# NG2092_RIGHT_OV9282.net
KiCad netlist of a schematic drawn in Altium Designer
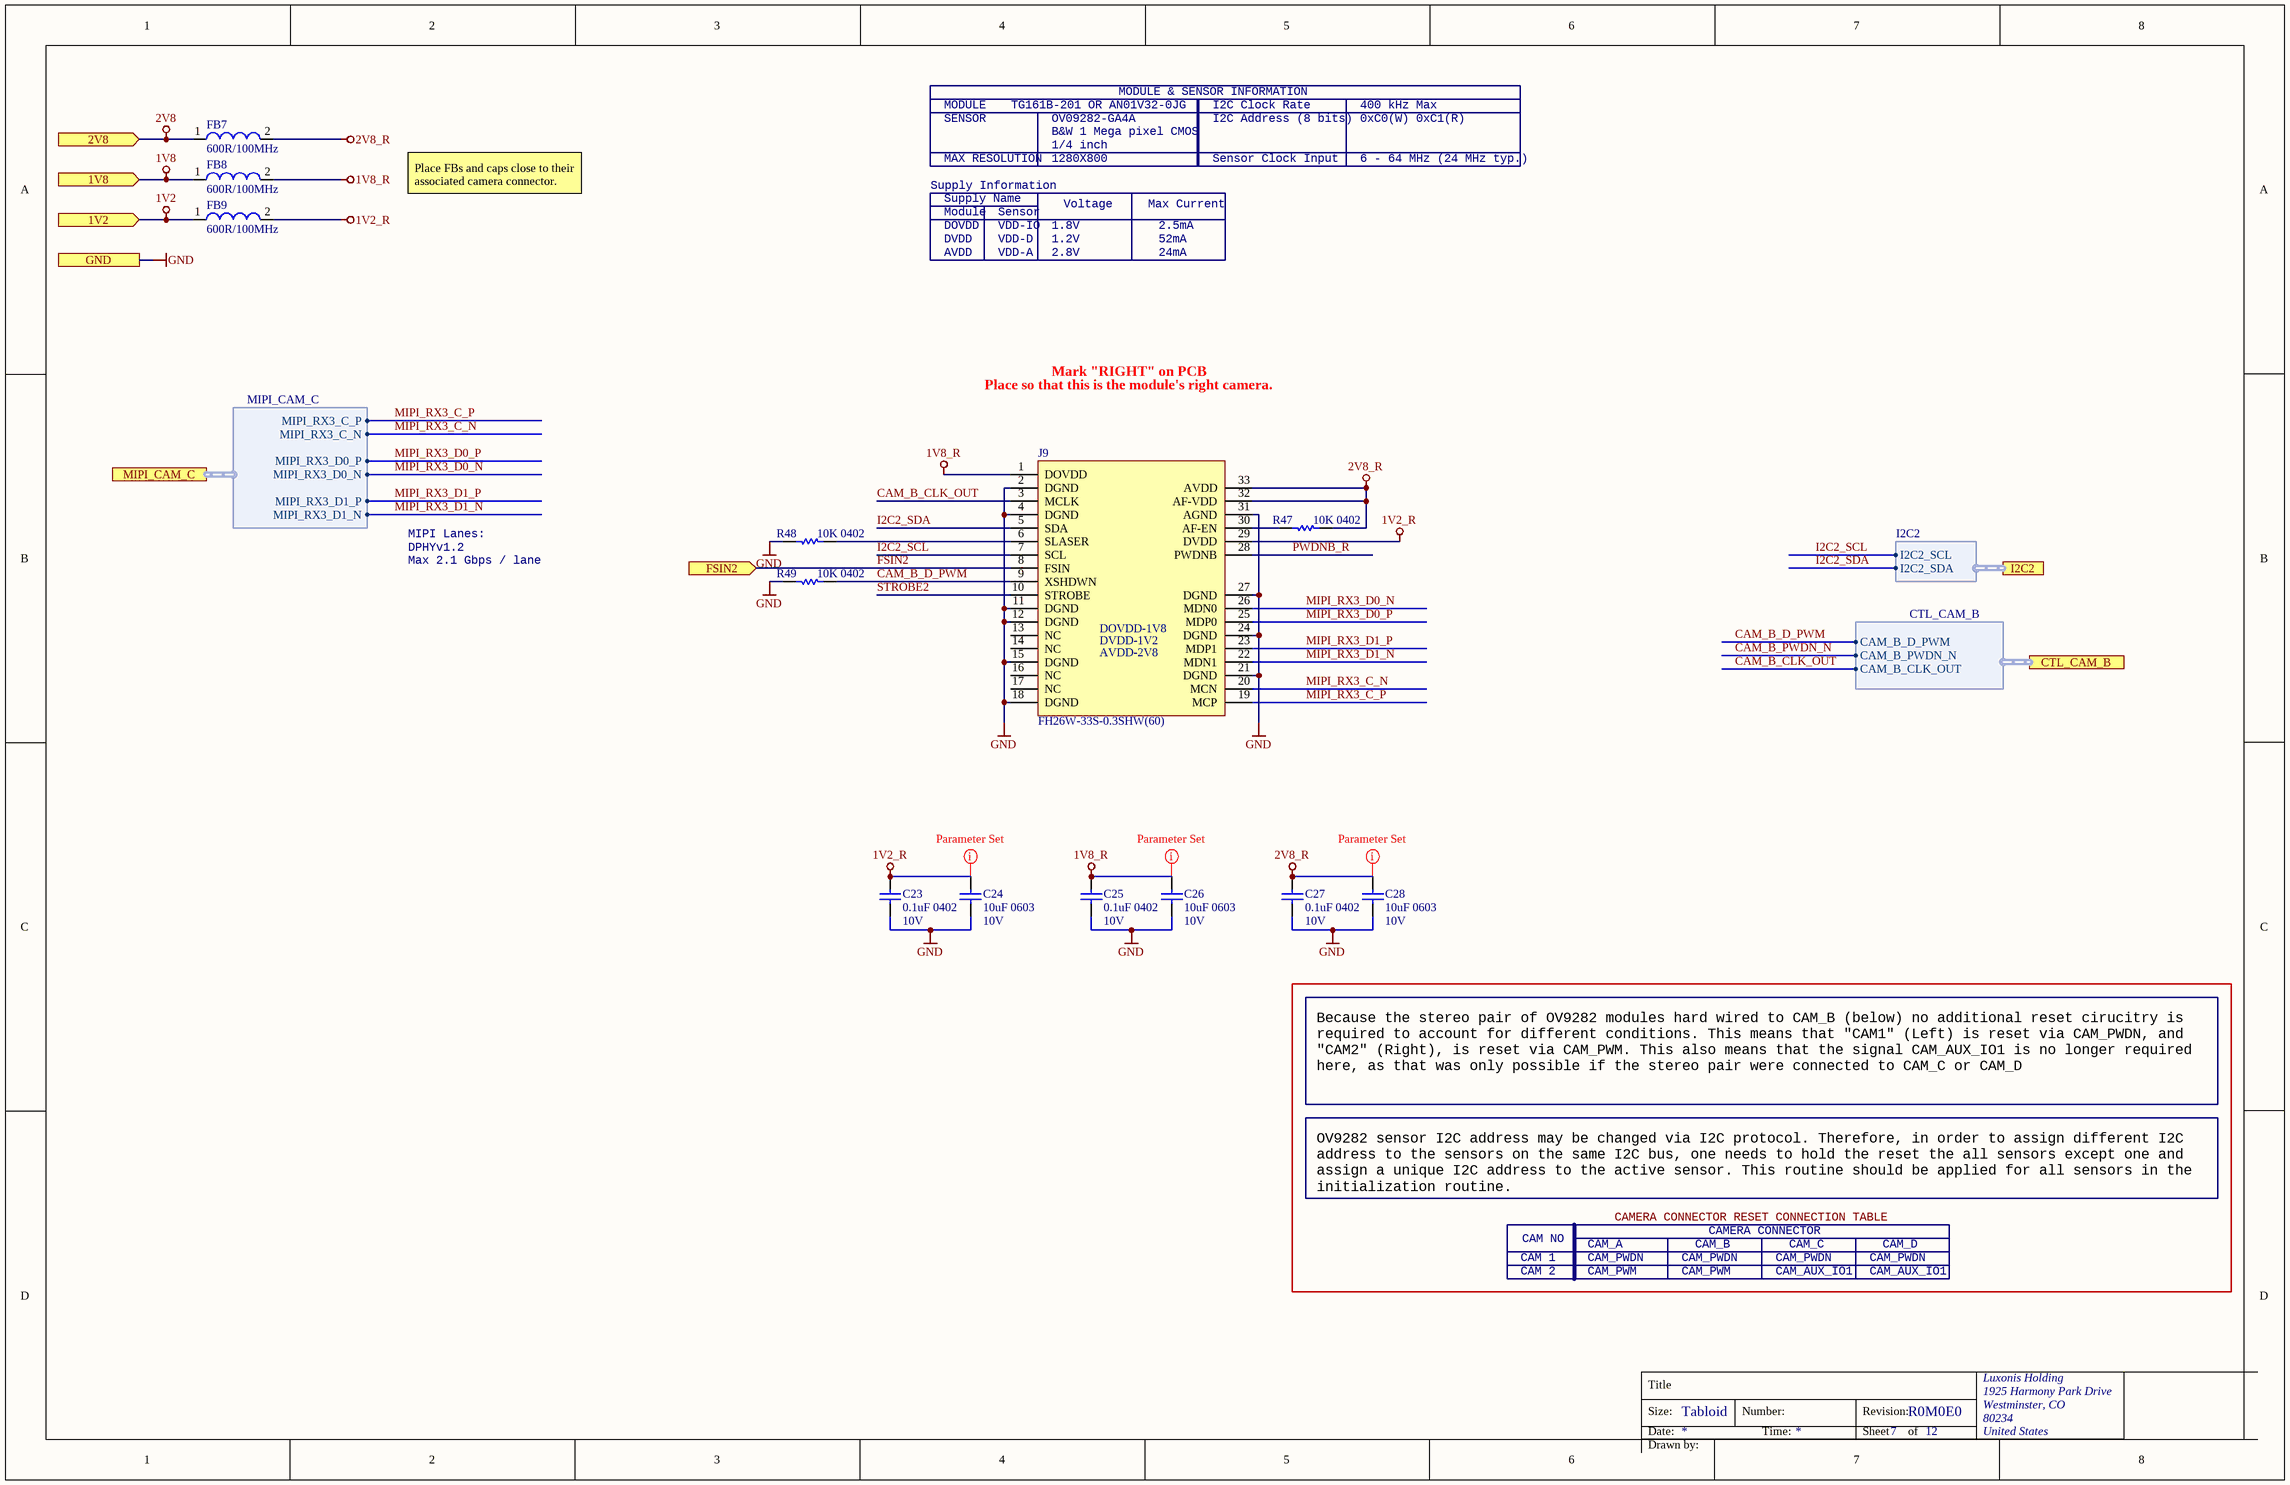
[diagram p0: NG2092_RIGHT_OV9282.SchDoc]

(export (version "E")
  (design (tool "Eeschema 10.0.6"))
  (components
    (comp (ref "C23")
      (value "0.1uF 0402")
      (footprint "CAP_Altium_Vault_Generic:CAPC0402(1005)70_L")
      (description "CAP CER 0.1UF 10V X7R 0402 5%")
      (fields (field (name "TOLERANCE") "5%") (field (name "VOLTAGE RATING") "10V"))
      (libsource (lib "LuxonisMaster") (part "GRM155R71A104JA01D"))
    )
    (comp (ref "C24")
      (value "10uF 0603")
      (footprint "CAP_Altium_Vault_Generic:CAPC0603(1608)100_L")
      (description "CAP CER 10UF 10V X5R 0603 20%")
      (fields (field (name "TOLERANCE") "20%") (field (name "VOLTAGE RATING") "10V"))
      (libsource (lib "LuxonisMaster") (part "GRM188R61A106ME69D"))
    )
    (comp (ref "C25")
      (value "0.1uF 0402")
      (footprint "CAP_Altium_Vault_Generic:CAPC0402(1005)70_L")
      (description "CAP CER 0.1UF 10V X7R 0402 5%")
      (fields (field (name "TOLERANCE") "5%") (field (name "VOLTAGE RATING") "10V"))
      (libsource (lib "LuxonisMaster") (part "GRM155R71A104JA01D"))
    )
    (comp (ref "C26")
      (value "10uF 0603")
      (footprint "CAP_Altium_Vault_Generic:CAPC0603(1608)100_L")
      (description "CAP CER 10UF 10V X5R 0603 20%")
      (fields (field (name "TOLERANCE") "20%") (field (name "VOLTAGE RATING") "10V"))
      (libsource (lib "LuxonisMaster") (part "GRM188R61A106ME69D"))
    )
    (comp (ref "C27")
      (value "0.1uF 0402")
      (footprint "CAP_Altium_Vault_Generic:CAPC0402(1005)70_L")
      (description "CAP CER 0.1UF 10V X7R 0402 5%")
      (fields (field (name "TOLERANCE") "5%") (field (name "VOLTAGE RATING") "10V"))
      (libsource (lib "LuxonisMaster") (part "GRM155R71A104JA01D"))
    )
    (comp (ref "C28")
      (value "10uF 0603")
      (footprint "CAP_Altium_Vault_Generic:CAPC0603(1608)100_L")
      (description "CAP CER 10UF 10V X5R 0603 20%")
      (fields (field (name "TOLERANCE") "20%") (field (name "VOLTAGE RATING") "10V"))
      (libsource (lib "LuxonisMaster") (part "GRM188R61A106ME69D"))
    )
    (comp (ref "FB7")
      (value "600R/100MHz")
      (footprint "LuxonisMaster:2508056017Y2")
      (description "FERRITE BEAD, 0.1OHM, 2A, 0805, 600R/100MHz")
      (fields (field (name "TOLERANCE") "25%"))
      (libsource (lib "LuxonisMaster") (part "2508056017Y2"))
    )
    (comp (ref "FB8")
      (value "600R/100MHz")
      (footprint "LuxonisMaster:2508056017Y2")
      (description "FERRITE BEAD, 0.1OHM, 2A, 0805, 600R/100MHz")
      (fields (field (name "TOLERANCE") "25%"))
      (libsource (lib "LuxonisMaster") (part "2508056017Y2"))
    )
    (comp (ref "FB9")
      (value "600R/100MHz")
      (footprint "LuxonisMaster:2508056017Y2")
      (description "FERRITE BEAD, 0.1OHM, 2A, 0805, 600R/100MHz")
      (fields (field (name "TOLERANCE") "25%"))
      (libsource (lib "LuxonisMaster") (part "2508056017Y2"))
    )
    (comp (ref "J9")
      (value "FH26W-33S-0.3SHW(60)")
      (footprint "AC-PY003-OV9282")
      (description "FFC/FPC Connector, 33 Contact(s), 1 Row(s), Female, Right Angle, Surface Mount Terminal")
      (libsource (lib "NG2092") (part "AC_PY003-OV9282_CON"))
    )
    (comp (ref "R47")
      (value "10K 0402")
      (footprint "RES_Altium_Vault_Generic:RESC0402(1005)_L")
      (fields (field (name "TOLERANCE") "1%"))
      (libsource (lib "LuxonisMaster") (part "RC0402FR-1310KL"))
    )
    (comp (ref "R48")
      (value "10K 0402")
      (footprint "RES_Altium_Vault_Generic:RESC0402(1005)_L")
      (fields (field (name "TOLERANCE") "1%"))
      (libsource (lib "LuxonisMaster") (part "RC0402FR-1310KL"))
    )
    (comp (ref "R49")
      (value "10K 0402")
      (footprint "RES_Altium_Vault_Generic:RESC0402(1005)_L")
      (fields (field (name "TOLERANCE") "1%"))
      (libsource (lib "LuxonisMaster") (part "RC0402FR-1310KL"))
    )
  )
  (nets
    (net (code "4") (name "/CAM_B_CLK_OUT") (class "Default")
      (node (ref "J9") (pin "3") (pinfunction "MCLK_3") (pintype "passive"))
    )
    (net (code "5") (name "/CAM_B_D_PWM") (class "Default")
      (node (ref "J9") (pin "9") (pinfunction "XSHDWN_9") (pintype "passive"))
      (node (ref "R49") (pin "1") (pinfunction "1_1") (pintype "passive"))
    )
    (net (code "7") (name "/FSIN2") (class "Default")
      (node (ref "J9") (pin "8") (pinfunction "FSIN_8") (pintype "passive"))
    )
    (net (code "8") (name "/I2C2_SCL") (class "Default")
      (node (ref "J9") (pin "7") (pinfunction "SCL_7") (pintype "passive"))
    )
    (net (code "9") (name "/I2C2_SDA") (class "Default")
      (node (ref "J9") (pin "5") (pinfunction "SDA_5") (pintype "passive"))
    )
    (net (code "10") (name "/MIPI_RX3_C_N") (class "Default")
      (node (ref "J9") (pin "20") (pinfunction "MCN_20") (pintype "passive"))
    )
    (net (code "11") (name "/MIPI_RX3_C_P") (class "Default")
      (node (ref "J9") (pin "19") (pinfunction "MCP_19") (pintype "passive"))
    )
    (net (code "12") (name "/MIPI_RX3_D0_N") (class "Default")
      (node (ref "J9") (pin "26") (pinfunction "MDN0_26") (pintype "passive"))
    )
    (net (code "13") (name "/MIPI_RX3_D0_P") (class "Default")
      (node (ref "J9") (pin "25") (pinfunction "MDP0_25") (pintype "passive"))
    )
    (net (code "14") (name "/MIPI_RX3_D1_N") (class "Default")
      (node (ref "J9") (pin "22") (pinfunction "MDN1_22") (pintype "passive"))
    )
    (net (code "15") (name "/MIPI_RX3_D1_P") (class "Default")
      (node (ref "J9") (pin "23") (pinfunction "MDP1_23") (pintype "passive"))
    )
    (net (code "16") (name "/PWDNB_R") (class "Default")
      (node (ref "J9") (pin "28") (pinfunction "PWDNB_28") (pintype "passive"))
    )
    (net (code "17") (name "/STROBE2") (class "Default")
      (node (ref "J9") (pin "10") (pinfunction "STROBE_10") (pintype "passive"))
    )
    (net (code "21") (name "1V2") (class "Default")
      (node (ref "FB9") (pin "1") (pinfunction "1_1") (pintype "passive"))
    )
    (net (code "22") (name "1V2_R") (class "Default")
      (node (ref "C23") (pin "2") (pinfunction "2_2") (pintype "passive"))
      (node (ref "C24") (pin "2") (pinfunction "2_2") (pintype "passive"))
      (node (ref "FB9") (pin "2") (pinfunction "2_2") (pintype "passive"))
      (node (ref "J9") (pin "29") (pinfunction "DVDD_29") (pintype "passive"))
    )
    (net (code "23") (name "1V8") (class "Default")
      (node (ref "FB8") (pin "1") (pinfunction "1_1") (pintype "passive"))
    )
    (net (code "24") (name "1V8_R") (class "Default")
      (node (ref "C25") (pin "2") (pinfunction "2_2") (pintype "passive"))
      (node (ref "C26") (pin "2") (pinfunction "2_2") (pintype "passive"))
      (node (ref "FB8") (pin "2") (pinfunction "2_2") (pintype "passive"))
      (node (ref "J9") (pin "1") (pinfunction "DOVDD_1") (pintype "passive"))
    )
    (net (code "25") (name "2V8") (class "Default")
      (node (ref "FB7") (pin "1") (pinfunction "1_1") (pintype "passive"))
    )
    (net (code "26") (name "2V8_R") (class "Default")
      (node (ref "C27") (pin "2") (pinfunction "2_2") (pintype "passive"))
      (node (ref "C28") (pin "2") (pinfunction "2_2") (pintype "passive"))
      (node (ref "FB7") (pin "2") (pinfunction "2_2") (pintype "passive"))
      (node (ref "J9") (pin "32") (pinfunction "AF-VDD_32") (pintype "passive"))
      (node (ref "J9") (pin "33") (pinfunction "AVDD_33") (pintype "passive"))
      (node (ref "R47") (pin "1") (pinfunction "1_1") (pintype "passive"))
    )
    (net (code "27") (name "GND") (class "Default")
      (node (ref "C23") (pin "1") (pinfunction "1_1") (pintype "passive"))
      (node (ref "C24") (pin "1") (pinfunction "1_1") (pintype "passive"))
      (node (ref "C25") (pin "1") (pinfunction "1_1") (pintype "passive"))
      (node (ref "C26") (pin "1") (pinfunction "1_1") (pintype "passive"))
      (node (ref "C27") (pin "1") (pinfunction "1_1") (pintype "passive"))
      (node (ref "C28") (pin "1") (pinfunction "1_1") (pintype "passive"))
      (node (ref "J9") (pin "11") (pinfunction "DGND_11") (pintype "passive"))
      (node (ref "J9") (pin "12") (pinfunction "DGND_12") (pintype "passive"))
      (node (ref "J9") (pin "15") (pinfunction "DGND_15") (pintype "passive"))
      (node (ref "J9") (pin "18") (pinfunction "DGND_18") (pintype "passive"))
      (node (ref "J9") (pin "2") (pinfunction "DGND_2") (pintype "passive"))
      (node (ref "J9") (pin "21") (pinfunction "DGND_21") (pintype "passive"))
      (node (ref "J9") (pin "24") (pinfunction "DGND_24") (pintype "passive"))
      (node (ref "J9") (pin "27") (pinfunction "DGND_27") (pintype "passive"))
      (node (ref "J9") (pin "31") (pinfunction "AGND_31") (pintype "passive"))
      (node (ref "J9") (pin "4") (pinfunction "DGND_4") (pintype "passive"))
      (node (ref "R48") (pin "2") (pinfunction "2_2") (pintype "passive"))
      (node (ref "R49") (pin "2") (pinfunction "2_2") (pintype "passive"))
    )
    (net (code "28") (name "Net-(J9-AF-EN)") (class "Default")
      (node (ref "J9") (pin "30") (pinfunction "AF-EN_30") (pintype "passive"))
      (node (ref "R47") (pin "2") (pinfunction "2_2") (pintype "passive"))
    )
    (net (code "29") (name "Net-(J9-SLASER)") (class "Default")
      (node (ref "J9") (pin "6") (pinfunction "SLASER_6") (pintype "passive"))
      (node (ref "R48") (pin "1") (pinfunction "1_1") (pintype "passive"))
    )
    (net (code "30") (name "unconnected-(J9-NC-Pad13)") (class "Default")
      (node (ref "J9") (pin "13") (pinfunction "NC_13") (pintype "passive"))
    )
    (net (code "31") (name "unconnected-(J9-NC-Pad14)") (class "Default")
      (node (ref "J9") (pin "14") (pinfunction "NC_14") (pintype "passive"))
    )
    (net (code "32") (name "unconnected-(J9-NC-Pad16)") (class "Default")
      (node (ref "J9") (pin "16") (pinfunction "NC_16") (pintype "passive"))
    )
    (net (code "33") (name "unconnected-(J9-NC-Pad17)") (class "Default")
      (node (ref "J9") (pin "17") (pinfunction "NC_17") (pintype "passive"))
    )
  )
)
